# 6502_C64_with_6526.net
KiCad netlist of a schematic drawn in EAGLE
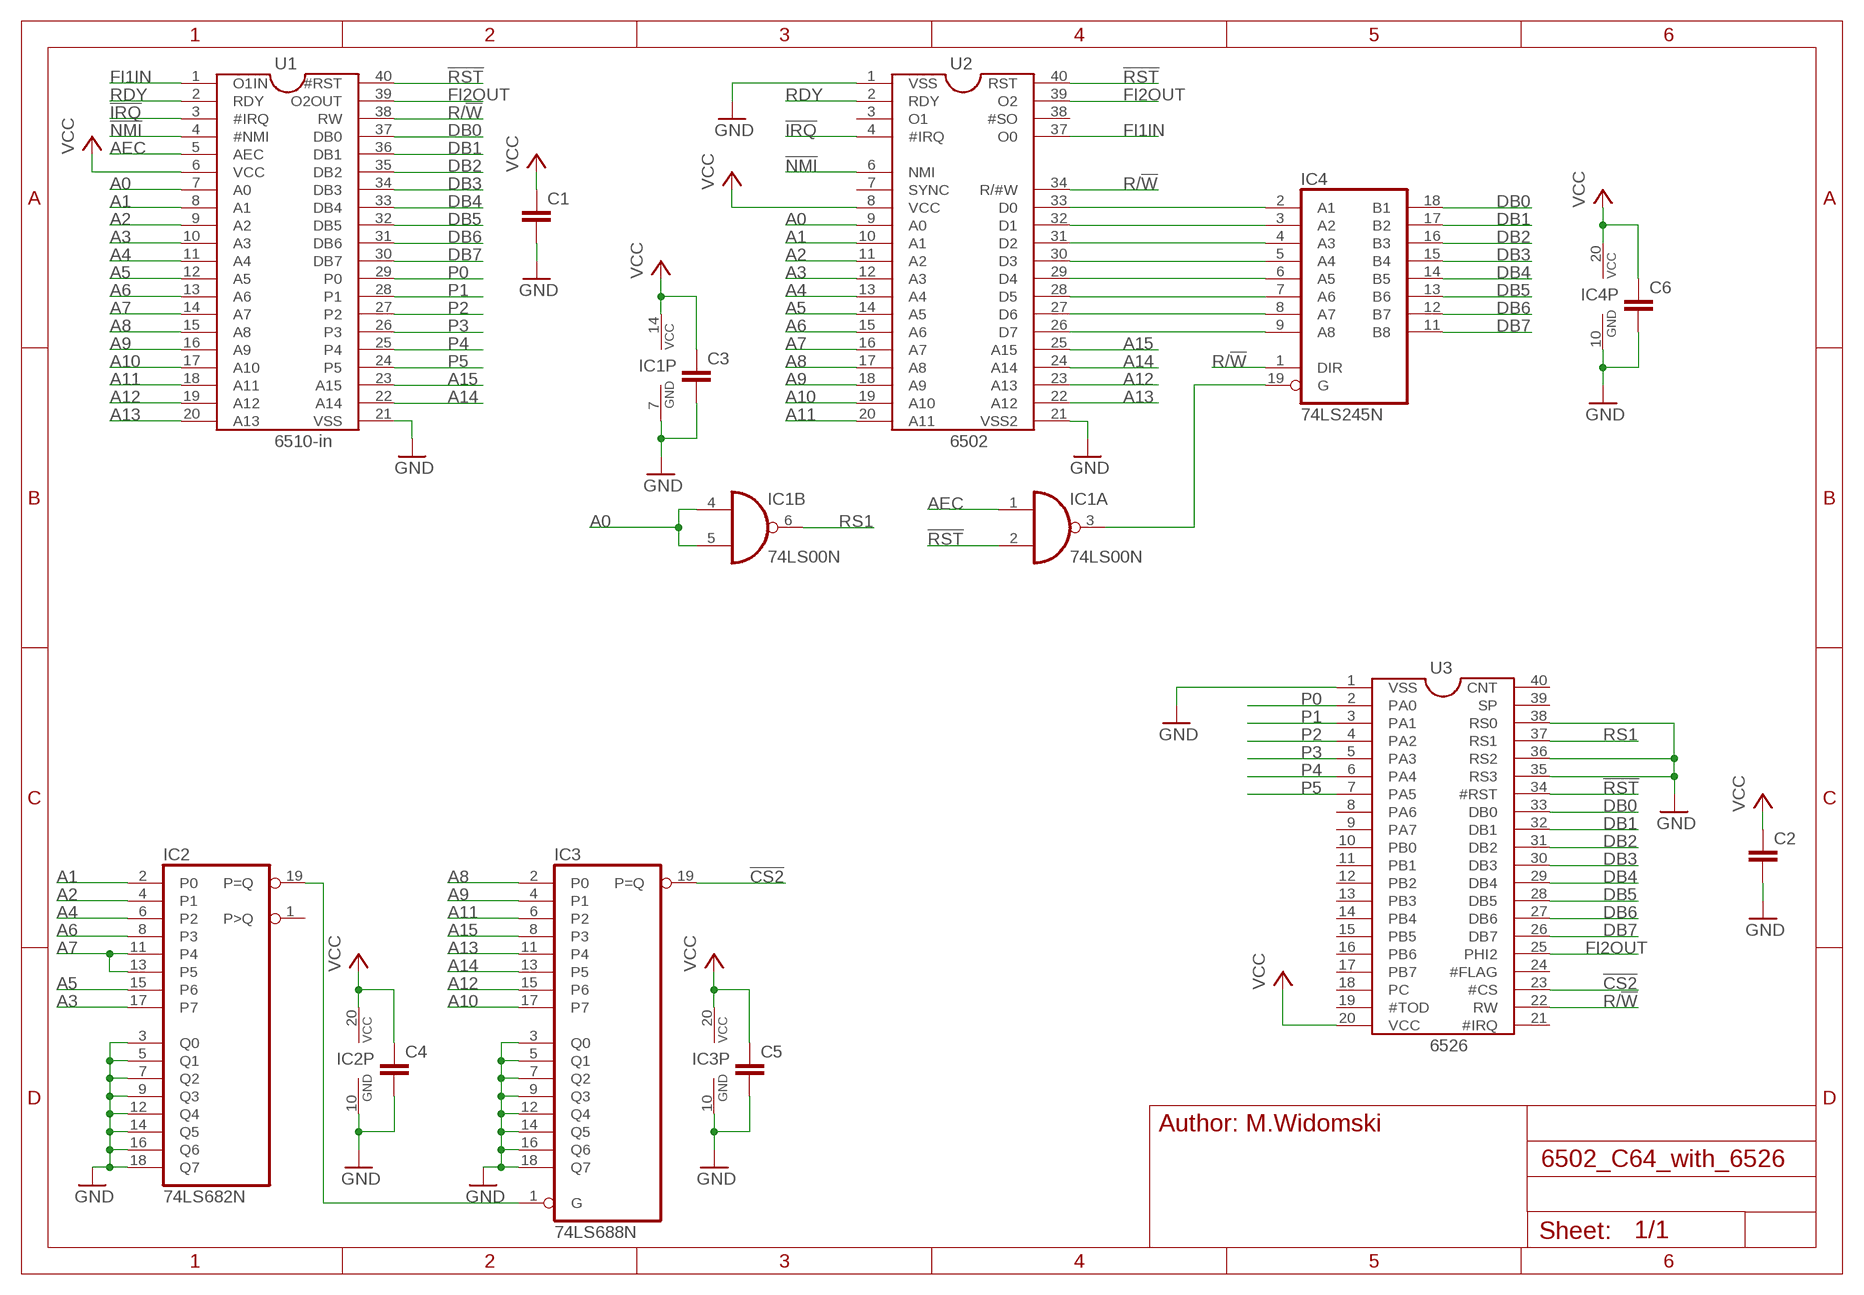
[diagram p0: schematic, sheet 1]

(export (version "E")
  (design (tool "Eeschema 10.0.6"))
  (components
    (comp (ref "C1")
      (value "C-EU025-025X050")
      (footprint "eagle-import:C025-025X050")
      (libsource (lib "eagle-import") (part "C-EU025-025X050"))
    )
    (comp (ref "C2")
      (value "C-EU025-025X050")
      (footprint "eagle-import:C025-025X050")
      (libsource (lib "eagle-import") (part "C-EU025-025X050"))
    )
    (comp (ref "C3")
      (value "C-EU025-025X050")
      (footprint "eagle-import:C025-025X050")
      (libsource (lib "eagle-import") (part "C-EU025-025X050"))
    )
    (comp (ref "C4")
      (value "C-EU025-025X050")
      (footprint "eagle-import:C025-025X050")
      (libsource (lib "eagle-import") (part "C-EU025-025X050"))
    )
    (comp (ref "C5")
      (value "C-EU025-025X050")
      (footprint "eagle-import:C025-025X050")
      (libsource (lib "eagle-import") (part "C-EU025-025X050"))
    )
    (comp (ref "C6")
      (value "C-EU025-025X050")
      (footprint "eagle-import:C025-025X050")
      (libsource (lib "eagle-import") (part "C-EU025-025X050"))
    )
    (comp (ref "IC1")
      (value "74LS00N")
      (footprint "eagle-import:DIL14")
      (libsource (lib "eagle-import") (part "7400NLS"))
    )
    (comp (ref "IC2")
      (value "74LS682N")
      (footprint "eagle-import:DIL20")
      (libsource (lib "eagle-import") (part "74682NLS"))
    )
    (comp (ref "IC3")
      (value "74LS688N")
      (footprint "eagle-import:DIL20")
      (libsource (lib "eagle-import") (part "74688NLS"))
    )
    (comp (ref "IC4")
      (value "74LS245N")
      (footprint "eagle-import:DIL20")
      (libsource (lib "eagle-import") (part "74245NLS"))
    )
    (comp (ref "U1")
      (value "6510-in")
      (footprint "eagle-import:DIL40")
      (libsource (lib "eagle-import") (part "6510"))
    )
    (comp (ref "U2")
      (value "6502")
      (footprint "eagle-import:DIL40")
      (libsource (lib "eagle-import") (part "6502"))
    )
    (comp (ref "U3")
      (value "6526")
      (footprint "eagle-import:DIL40")
      (libsource (lib "eagle-import") (part "6526"))
    )
  )
  (nets
    (net (code "1") (name "/A0") (class "Default")
      (node (ref "IC1") (pin "4") (pinfunction "I0_4") (pintype "input"))
      (node (ref "IC1") (pin "5") (pinfunction "I1_5") (pintype "input"))
      (node (ref "U1") (pin "7") (pinfunction "A0_7") (pintype "bidirectional"))
      (node (ref "U2") (pin "9") (pinfunction "A0_9") (pintype "bidirectional"))
    )
    (net (code "2") (name "/A1") (class "Default")
      (node (ref "IC2") (pin "2") (pinfunction "P0_2") (pintype "input"))
      (node (ref "U1") (pin "8") (pinfunction "A1_8") (pintype "bidirectional"))
      (node (ref "U2") (pin "10") (pinfunction "A1_10") (pintype "bidirectional"))
    )
    (net (code "3") (name "/A2") (class "Default")
      (node (ref "IC2") (pin "4") (pinfunction "P1_4") (pintype "input"))
      (node (ref "U1") (pin "9") (pinfunction "A2_9") (pintype "bidirectional"))
      (node (ref "U2") (pin "11") (pinfunction "A2_11") (pintype "bidirectional"))
    )
    (net (code "4") (name "/A3") (class "Default")
      (node (ref "IC2") (pin "17") (pinfunction "P7_17") (pintype "input"))
      (node (ref "U1") (pin "10") (pinfunction "A3_10") (pintype "bidirectional"))
      (node (ref "U2") (pin "12") (pinfunction "A3_12") (pintype "bidirectional"))
    )
    (net (code "5") (name "/A4") (class "Default")
      (node (ref "IC2") (pin "6") (pinfunction "P2_6") (pintype "input"))
      (node (ref "U1") (pin "11") (pinfunction "A4_11") (pintype "bidirectional"))
      (node (ref "U2") (pin "13") (pinfunction "A4_13") (pintype "bidirectional"))
    )
    (net (code "6") (name "/A5") (class "Default")
      (node (ref "IC2") (pin "15") (pinfunction "P6_15") (pintype "input"))
      (node (ref "U1") (pin "12") (pinfunction "A5_12") (pintype "bidirectional"))
      (node (ref "U2") (pin "14") (pinfunction "A5_14") (pintype "bidirectional"))
    )
    (net (code "7") (name "/A6") (class "Default")
      (node (ref "IC2") (pin "8") (pinfunction "P3_8") (pintype "input"))
      (node (ref "U1") (pin "13") (pinfunction "A6_13") (pintype "bidirectional"))
      (node (ref "U2") (pin "15") (pinfunction "A6_15") (pintype "bidirectional"))
    )
    (net (code "8") (name "/A7") (class "Default")
      (node (ref "IC2") (pin "11") (pinfunction "P4_11") (pintype "input"))
      (node (ref "IC2") (pin "13") (pinfunction "P5_13") (pintype "input"))
      (node (ref "U1") (pin "14") (pinfunction "A7_14") (pintype "bidirectional"))
      (node (ref "U2") (pin "16") (pinfunction "A7_16") (pintype "bidirectional"))
    )
    (net (code "9") (name "/A8") (class "Default")
      (node (ref "IC3") (pin "2") (pinfunction "P0_2") (pintype "input"))
      (node (ref "U1") (pin "15") (pinfunction "A8_15") (pintype "bidirectional"))
      (node (ref "U2") (pin "17") (pinfunction "A8_17") (pintype "bidirectional"))
    )
    (net (code "10") (name "/A9") (class "Default")
      (node (ref "IC3") (pin "4") (pinfunction "P1_4") (pintype "input"))
      (node (ref "U1") (pin "16") (pinfunction "A9_16") (pintype "bidirectional"))
      (node (ref "U2") (pin "18") (pinfunction "A9_18") (pintype "bidirectional"))
    )
    (net (code "11") (name "/A10") (class "Default")
      (node (ref "IC3") (pin "17") (pinfunction "P7_17") (pintype "input"))
      (node (ref "U1") (pin "17") (pinfunction "A10_17") (pintype "bidirectional"))
      (node (ref "U2") (pin "19") (pinfunction "A10_19") (pintype "bidirectional"))
    )
    (net (code "12") (name "/A11") (class "Default")
      (node (ref "IC3") (pin "6") (pinfunction "P2_6") (pintype "input"))
      (node (ref "U1") (pin "18") (pinfunction "A11_18") (pintype "bidirectional"))
      (node (ref "U2") (pin "20") (pinfunction "A11_20") (pintype "bidirectional"))
    )
    (net (code "13") (name "/A12") (class "Default")
      (node (ref "IC3") (pin "15") (pinfunction "P6_15") (pintype "input"))
      (node (ref "U1") (pin "19") (pinfunction "A12_19") (pintype "bidirectional"))
      (node (ref "U2") (pin "23") (pinfunction "A13_23") (pintype "bidirectional"))
    )
    (net (code "14") (name "/A13") (class "Default")
      (node (ref "IC3") (pin "11") (pinfunction "P4_11") (pintype "input"))
      (node (ref "U1") (pin "20") (pinfunction "A13_20") (pintype "bidirectional"))
      (node (ref "U2") (pin "22") (pinfunction "A12_22") (pintype "bidirectional"))
    )
    (net (code "15") (name "/A14") (class "Default")
      (node (ref "IC3") (pin "13") (pinfunction "P5_13") (pintype "input"))
      (node (ref "U1") (pin "22") (pinfunction "A14_22") (pintype "bidirectional"))
      (node (ref "U2") (pin "24") (pinfunction "A14_24") (pintype "bidirectional"))
    )
    (net (code "16") (name "/A15") (class "Default")
      (node (ref "IC3") (pin "8") (pinfunction "P3_8") (pintype "input"))
      (node (ref "U1") (pin "23") (pinfunction "A15_23") (pintype "bidirectional"))
      (node (ref "U2") (pin "25") (pinfunction "A15_25") (pintype "bidirectional"))
    )
    (net (code "17") (name "/AEC") (class "Default")
      (node (ref "IC1") (pin "1") (pinfunction "I0_1") (pintype "input"))
      (node (ref "U1") (pin "5") (pinfunction "AEC_5") (pintype "bidirectional"))
    )
    (net (code "18") (name "/DB0") (class "Default")
      (node (ref "IC4") (pin "18") (pinfunction "B1_18") (pintype "bidirectional"))
      (node (ref "U1") (pin "37") (pinfunction "DB0_37") (pintype "bidirectional"))
      (node (ref "U3") (pin "33") (pinfunction "DB0_33") (pintype "bidirectional"))
    )
    (net (code "19") (name "/DB1") (class "Default")
      (node (ref "IC4") (pin "17") (pinfunction "B2_17") (pintype "bidirectional"))
      (node (ref "U1") (pin "36") (pinfunction "DB1_36") (pintype "bidirectional"))
      (node (ref "U3") (pin "32") (pinfunction "DB1_32") (pintype "bidirectional"))
    )
    (net (code "20") (name "/DB2") (class "Default")
      (node (ref "IC4") (pin "16") (pinfunction "B3_16") (pintype "bidirectional"))
      (node (ref "U1") (pin "35") (pinfunction "DB2_35") (pintype "bidirectional"))
      (node (ref "U3") (pin "31") (pinfunction "DB2_31") (pintype "bidirectional"))
    )
    (net (code "21") (name "/DB3") (class "Default")
      (node (ref "IC4") (pin "15") (pinfunction "B4_15") (pintype "bidirectional"))
      (node (ref "U1") (pin "34") (pinfunction "DB3_34") (pintype "bidirectional"))
      (node (ref "U3") (pin "30") (pinfunction "DB3_30") (pintype "bidirectional"))
    )
    (net (code "22") (name "/DB4") (class "Default")
      (node (ref "IC4") (pin "14") (pinfunction "B5_14") (pintype "bidirectional"))
      (node (ref "U1") (pin "33") (pinfunction "DB4_33") (pintype "bidirectional"))
      (node (ref "U3") (pin "29") (pinfunction "DB4_29") (pintype "bidirectional"))
    )
    (net (code "23") (name "/DB5") (class "Default")
      (node (ref "IC4") (pin "13") (pinfunction "B6_13") (pintype "bidirectional"))
      (node (ref "U1") (pin "32") (pinfunction "DB5_32") (pintype "bidirectional"))
      (node (ref "U3") (pin "28") (pinfunction "DB5_28") (pintype "bidirectional"))
    )
    (net (code "24") (name "/DB6") (class "Default")
      (node (ref "IC4") (pin "12") (pinfunction "B7_12") (pintype "bidirectional"))
      (node (ref "U1") (pin "31") (pinfunction "DB6_31") (pintype "bidirectional"))
      (node (ref "U3") (pin "27") (pinfunction "DB6_27") (pintype "bidirectional"))
    )
    (net (code "25") (name "/DB7") (class "Default")
      (node (ref "IC4") (pin "11") (pinfunction "B8_11") (pintype "bidirectional"))
      (node (ref "U1") (pin "30") (pinfunction "DB7_30") (pintype "bidirectional"))
      (node (ref "U3") (pin "26") (pinfunction "DB7_26") (pintype "bidirectional"))
    )
    (net (code "26") (name "/FI1IN") (class "Default")
      (node (ref "U1") (pin "1") (pinfunction "O1IN_1") (pintype "bidirectional"))
      (node (ref "U2") (pin "37") (pinfunction "O0_37") (pintype "bidirectional"))
    )
    (net (code "27") (name "/FI2OUT") (class "Default")
      (node (ref "U1") (pin "39") (pinfunction "O2OUT_39") (pintype "bidirectional"))
      (node (ref "U2") (pin "39") (pinfunction "O2_39") (pintype "bidirectional"))
      (node (ref "U3") (pin "25") (pinfunction "PHI2_25") (pintype "bidirectional"))
    )
    (net (code "28") (name "/P0") (class "Default")
      (node (ref "U1") (pin "29") (pinfunction "P0_29") (pintype "bidirectional"))
      (node (ref "U3") (pin "2") (pinfunction "PA0_2") (pintype "bidirectional"))
    )
    (net (code "29") (name "/P1") (class "Default")
      (node (ref "U1") (pin "28") (pinfunction "P1_28") (pintype "bidirectional"))
      (node (ref "U3") (pin "3") (pinfunction "PA1_3") (pintype "bidirectional"))
    )
    (net (code "30") (name "/P2") (class "Default")
      (node (ref "U1") (pin "27") (pinfunction "P2_27") (pintype "bidirectional"))
      (node (ref "U3") (pin "4") (pinfunction "PA2_4") (pintype "bidirectional"))
    )
    (net (code "31") (name "/P3") (class "Default")
      (node (ref "U1") (pin "26") (pinfunction "P3_26") (pintype "bidirectional"))
      (node (ref "U3") (pin "5") (pinfunction "PA3_5") (pintype "bidirectional"))
    )
    (net (code "32") (name "/P4") (class "Default")
      (node (ref "U1") (pin "25") (pinfunction "P4_25") (pintype "bidirectional"))
      (node (ref "U3") (pin "6") (pinfunction "PA4_6") (pintype "bidirectional"))
    )
    (net (code "33") (name "/P5") (class "Default")
      (node (ref "U1") (pin "24") (pinfunction "P5_24") (pintype "bidirectional"))
      (node (ref "U3") (pin "7") (pinfunction "PA5_7") (pintype "bidirectional"))
    )
    (net (code "34") (name "/RDY") (class "Default")
      (node (ref "U1") (pin "2") (pinfunction "RDY_2") (pintype "bidirectional"))
      (node (ref "U2") (pin "2") (pinfunction "RDY_2") (pintype "bidirectional"))
    )
    (net (code "35") (name "/RS1") (class "Default")
      (node (ref "IC1") (pin "6") (pinfunction "O_6") (pintype "output"))
      (node (ref "U3") (pin "37") (pinfunction "RS1_37") (pintype "bidirectional"))
    )
    (net (code "36") (name "/R{slash}~{W}") (class "Default")
      (node (ref "IC4") (pin "1") (pinfunction "DIR_1") (pintype "input"))
      (node (ref "U1") (pin "38") (pinfunction "RW_38") (pintype "bidirectional"))
      (node (ref "U2") (pin "34") (pinfunction "R/#W_34") (pintype "bidirectional"))
      (node (ref "U3") (pin "22") (pinfunction "RW_22") (pintype "bidirectional"))
    )
    (net (code "37") (name "/~{CS2}") (class "Default")
      (node (ref "IC3") (pin "19") (pinfunction "P=Q_19") (pintype "output"))
      (node (ref "U3") (pin "23") (pinfunction "#CS_23") (pintype "bidirectional"))
    )
    (net (code "38") (name "/~{IRQ}") (class "Default")
      (node (ref "U1") (pin "3") (pinfunction "#IRQ_3") (pintype "bidirectional"))
      (node (ref "U2") (pin "4") (pinfunction "#IRQ_4") (pintype "bidirectional"))
    )
    (net (code "39") (name "/~{NMI}") (class "Default")
      (node (ref "U1") (pin "4") (pinfunction "#NMI_4") (pintype "bidirectional"))
      (node (ref "U2") (pin "6") (pinfunction "NMI_6") (pintype "bidirectional"))
    )
    (net (code "40") (name "/~{RST}") (class "Default")
      (node (ref "IC1") (pin "2") (pinfunction "I1_2") (pintype "input"))
      (node (ref "U1") (pin "40") (pinfunction "#RST_40") (pintype "bidirectional"))
      (node (ref "U2") (pin "40") (pinfunction "RST_40") (pintype "bidirectional"))
      (node (ref "U3") (pin "34") (pinfunction "#RST_34") (pintype "bidirectional"))
    )
    (net (code "41") (name "GND") (class "Default")
      (node (ref "C1") (pin "2") (pinfunction "2_2") (pintype "passive"))
      (node (ref "C2") (pin "2") (pinfunction "2_2") (pintype "passive"))
      (node (ref "C3") (pin "2") (pinfunction "2_2") (pintype "passive"))
      (node (ref "C4") (pin "2") (pinfunction "2_2") (pintype "passive"))
      (node (ref "C5") (pin "2") (pinfunction "2_2") (pintype "passive"))
      (node (ref "C6") (pin "2") (pinfunction "2_2") (pintype "passive"))
      (node (ref "IC1") (pin "7") (pinfunction "GND_7") (pintype "power_in"))
      (node (ref "IC2") (pin "10") (pinfunction "GND_10") (pintype "power_in"))
      (node (ref "IC2") (pin "12") (pinfunction "Q4_12") (pintype "input"))
      (node (ref "IC2") (pin "14") (pinfunction "Q5_14") (pintype "input"))
      (node (ref "IC2") (pin "16") (pinfunction "Q6_16") (pintype "input"))
      (node (ref "IC2") (pin "18") (pinfunction "Q7_18") (pintype "input"))
      (node (ref "IC2") (pin "3") (pinfunction "Q0_3") (pintype "input"))
      (node (ref "IC2") (pin "5") (pinfunction "Q1_5") (pintype "input"))
      (node (ref "IC2") (pin "7") (pinfunction "Q2_7") (pintype "input"))
      (node (ref "IC2") (pin "9") (pinfunction "Q3_9") (pintype "input"))
      (node (ref "IC3") (pin "10") (pinfunction "GND_10") (pintype "power_in"))
      (node (ref "IC3") (pin "12") (pinfunction "Q4_12") (pintype "input"))
      (node (ref "IC3") (pin "14") (pinfunction "Q5_14") (pintype "input"))
      (node (ref "IC3") (pin "16") (pinfunction "Q6_16") (pintype "input"))
      (node (ref "IC3") (pin "18") (pinfunction "Q7_18") (pintype "input"))
      (node (ref "IC3") (pin "3") (pinfunction "Q0_3") (pintype "input"))
      (node (ref "IC3") (pin "5") (pinfunction "Q1_5") (pintype "input"))
      (node (ref "IC3") (pin "7") (pinfunction "Q2_7") (pintype "input"))
      (node (ref "IC3") (pin "9") (pinfunction "Q3_9") (pintype "input"))
      (node (ref "IC4") (pin "10") (pinfunction "GND_10") (pintype "power_in"))
      (node (ref "U1") (pin "21") (pinfunction "VSS_21") (pintype "bidirectional"))
      (node (ref "U2") (pin "1") (pinfunction "VSS_1") (pintype "bidirectional"))
      (node (ref "U2") (pin "21") (pinfunction "VSS2_21") (pintype "bidirectional"))
      (node (ref "U3") (pin "1") (pinfunction "VSS_1") (pintype "bidirectional"))
      (node (ref "U3") (pin "35") (pinfunction "RS3_35") (pintype "bidirectional"))
      (node (ref "U3") (pin "36") (pinfunction "RS2_36") (pintype "bidirectional"))
      (node (ref "U3") (pin "38") (pinfunction "RS0_38") (pintype "bidirectional"))
    )
    (net (code "42") (name "Net-(IC1A-O)") (class "Default")
      (node (ref "IC1") (pin "3") (pinfunction "O_3") (pintype "output"))
      (node (ref "IC4") (pin "19") (pinfunction "G_19") (pintype "input"))
    )
    (net (code "43") (name "Net-(IC2A-P=Q)") (class "Default")
      (node (ref "IC2") (pin "19") (pinfunction "P=Q_19") (pintype "output"))
      (node (ref "IC3") (pin "1") (pinfunction "G_1") (pintype "input"))
    )
    (net (code "44") (name "Net-(IC4A-A1)") (class "Default")
      (node (ref "IC4") (pin "2") (pinfunction "A1_2") (pintype "bidirectional"))
      (node (ref "U2") (pin "33") (pinfunction "D0_33") (pintype "bidirectional"))
    )
    (net (code "45") (name "Net-(IC4A-A2)") (class "Default")
      (node (ref "IC4") (pin "3") (pinfunction "A2_3") (pintype "bidirectional"))
      (node (ref "U2") (pin "32") (pinfunction "D1_32") (pintype "bidirectional"))
    )
    (net (code "46") (name "Net-(IC4A-A3)") (class "Default")
      (node (ref "IC4") (pin "4") (pinfunction "A3_4") (pintype "bidirectional"))
      (node (ref "U2") (pin "31") (pinfunction "D2_31") (pintype "bidirectional"))
    )
    (net (code "47") (name "Net-(IC4A-A4)") (class "Default")
      (node (ref "IC4") (pin "5") (pinfunction "A4_5") (pintype "bidirectional"))
      (node (ref "U2") (pin "30") (pinfunction "D3_30") (pintype "bidirectional"))
    )
    (net (code "48") (name "Net-(IC4A-A5)") (class "Default")
      (node (ref "IC4") (pin "6") (pinfunction "A5_6") (pintype "bidirectional"))
      (node (ref "U2") (pin "29") (pinfunction "D4_29") (pintype "bidirectional"))
    )
    (net (code "49") (name "Net-(IC4A-A6)") (class "Default")
      (node (ref "IC4") (pin "7") (pinfunction "A6_7") (pintype "bidirectional"))
      (node (ref "U2") (pin "28") (pinfunction "D5_28") (pintype "bidirectional"))
    )
    (net (code "50") (name "Net-(IC4A-A7)") (class "Default")
      (node (ref "IC4") (pin "8") (pinfunction "A7_8") (pintype "bidirectional"))
      (node (ref "U2") (pin "27") (pinfunction "D6_27") (pintype "bidirectional"))
    )
    (net (code "51") (name "Net-(IC4A-A8)") (class "Default")
      (node (ref "IC4") (pin "9") (pinfunction "A8_9") (pintype "bidirectional"))
      (node (ref "U2") (pin "26") (pinfunction "D7_26") (pintype "bidirectional"))
    )
    (net (code "52") (name "VCC") (class "Default")
      (node (ref "C1") (pin "1") (pinfunction "1_1") (pintype "passive"))
      (node (ref "C2") (pin "1") (pinfunction "1_1") (pintype "passive"))
      (node (ref "C3") (pin "1") (pinfunction "1_1") (pintype "passive"))
      (node (ref "C4") (pin "1") (pinfunction "1_1") (pintype "passive"))
      (node (ref "C5") (pin "1") (pinfunction "1_1") (pintype "passive"))
      (node (ref "C6") (pin "1") (pinfunction "1_1") (pintype "passive"))
      (node (ref "IC1") (pin "14") (pinfunction "VCC_14") (pintype "power_in"))
      (node (ref "IC2") (pin "20") (pinfunction "VCC_20") (pintype "power_in"))
      (node (ref "IC3") (pin "20") (pinfunction "VCC_20") (pintype "power_in"))
      (node (ref "IC4") (pin "20") (pinfunction "VCC_20") (pintype "power_in"))
      (node (ref "U1") (pin "6") (pinfunction "VCC_6") (pintype "bidirectional"))
      (node (ref "U2") (pin "8") (pinfunction "VCC_8") (pintype "bidirectional"))
      (node (ref "U3") (pin "20") (pinfunction "VCC_20") (pintype "bidirectional"))
    )
    (net (code "53") (name "unconnected-(IC2A-P>Q-Pad1)") (class "Default")
      (node (ref "IC2") (pin "1") (pinfunction "P>Q_1") (pintype "output"))
    )
    (net (code "54") (name "unconnected-(U2-#SO-Pad38)") (class "Default")
      (node (ref "U2") (pin "38") (pinfunction "#SO_38") (pintype "bidirectional"))
    )
    (net (code "55") (name "unconnected-(U2-O1-Pad3)") (class "Default")
      (node (ref "U2") (pin "3") (pinfunction "O1_3") (pintype "bidirectional"))
    )
    (net (code "56") (name "unconnected-(U2-SYNC-Pad7)") (class "Default")
      (node (ref "U2") (pin "7") (pinfunction "SYNC_7") (pintype "bidirectional"))
    )
    (net (code "57") (name "unconnected-(U3-#FLAG-Pad24)") (class "Default")
      (node (ref "U3") (pin "24") (pinfunction "#FLAG_24") (pintype "bidirectional"))
    )
    (net (code "58") (name "unconnected-(U3-#IRQ-Pad21)") (class "Default")
      (node (ref "U3") (pin "21") (pinfunction "#IRQ_21") (pintype "bidirectional"))
    )
    (net (code "59") (name "unconnected-(U3-#TOD-Pad19)") (class "Default")
      (node (ref "U3") (pin "19") (pinfunction "#TOD_19") (pintype "bidirectional"))
    )
    (net (code "60") (name "unconnected-(U3-CNT-Pad40)") (class "Default")
      (node (ref "U3") (pin "40") (pinfunction "CNT_40") (pintype "bidirectional"))
    )
    (net (code "61") (name "unconnected-(U3-PA6-Pad8)") (class "Default")
      (node (ref "U3") (pin "8") (pinfunction "PA6_8") (pintype "bidirectional"))
    )
    (net (code "62") (name "unconnected-(U3-PA7-Pad9)") (class "Default")
      (node (ref "U3") (pin "9") (pinfunction "PA7_9") (pintype "bidirectional"))
    )
    (net (code "63") (name "unconnected-(U3-PB0-Pad10)") (class "Default")
      (node (ref "U3") (pin "10") (pinfunction "PB0_10") (pintype "bidirectional"))
    )
    (net (code "64") (name "unconnected-(U3-PB1-Pad11)") (class "Default")
      (node (ref "U3") (pin "11") (pinfunction "PB1_11") (pintype "bidirectional"))
    )
    (net (code "65") (name "unconnected-(U3-PB2-Pad12)") (class "Default")
      (node (ref "U3") (pin "12") (pinfunction "PB2_12") (pintype "bidirectional"))
    )
    (net (code "66") (name "unconnected-(U3-PB3-Pad13)") (class "Default")
      (node (ref "U3") (pin "13") (pinfunction "PB3_13") (pintype "bidirectional"))
    )
    (net (code "67") (name "unconnected-(U3-PB4-Pad14)") (class "Default")
      (node (ref "U3") (pin "14") (pinfunction "PB4_14") (pintype "bidirectional"))
    )
    (net (code "68") (name "unconnected-(U3-PB5-Pad15)") (class "Default")
      (node (ref "U3") (pin "15") (pinfunction "PB5_15") (pintype "bidirectional"))
    )
    (net (code "69") (name "unconnected-(U3-PB6-Pad16)") (class "Default")
      (node (ref "U3") (pin "16") (pinfunction "PB6_16") (pintype "bidirectional"))
    )
    (net (code "70") (name "unconnected-(U3-PB7-Pad17)") (class "Default")
      (node (ref "U3") (pin "17") (pinfunction "PB7_17") (pintype "bidirectional"))
    )
    (net (code "71") (name "unconnected-(U3-PC-Pad18)") (class "Default")
      (node (ref "U3") (pin "18") (pinfunction "PC_18") (pintype "bidirectional"))
    )
    (net (code "72") (name "unconnected-(U3-SP-Pad39)") (class "Default")
      (node (ref "U3") (pin "39") (pinfunction "SP_39") (pintype "bidirectional"))
    )
  )
)
